# darwin-radio.net
KiCad netlist of a schematic drawn in EAGLE
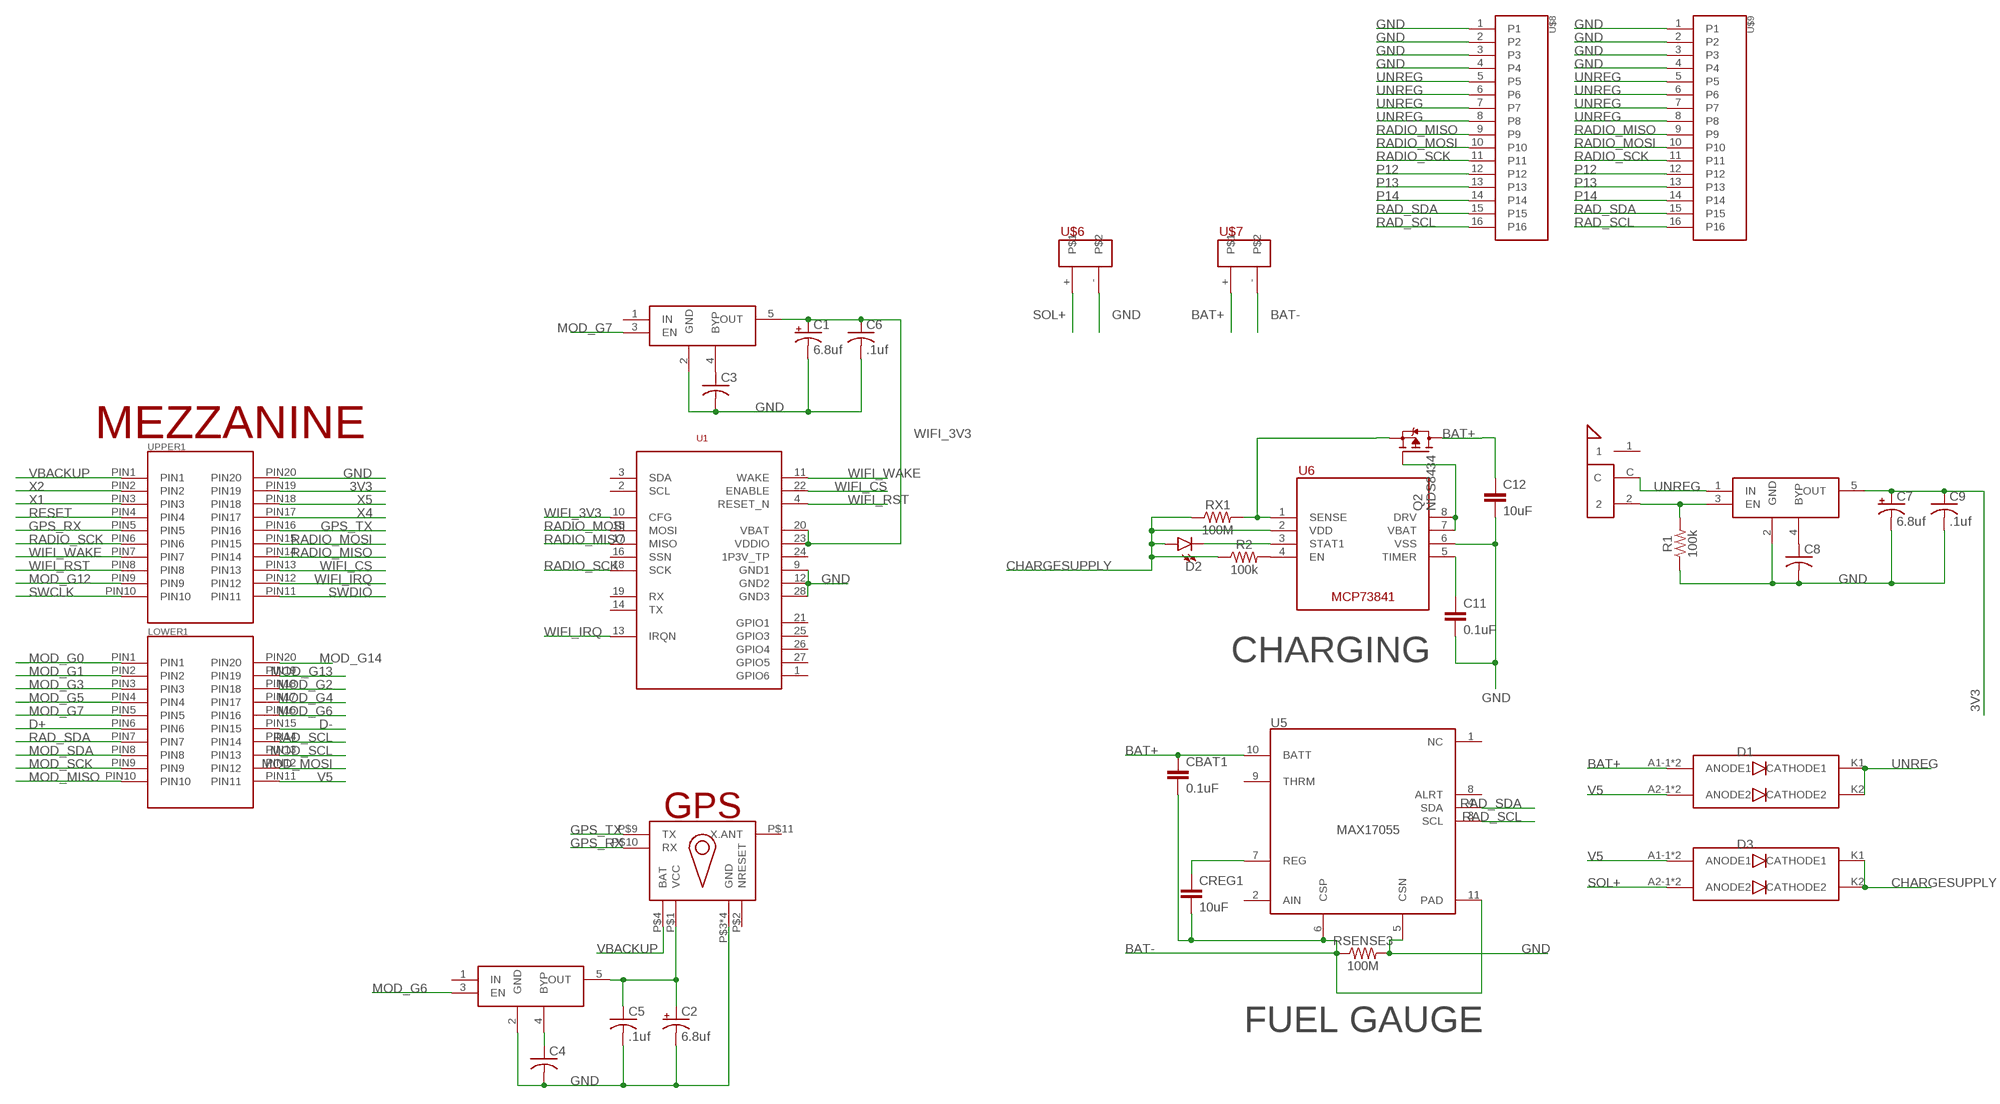
[diagram p0: schematic, sheet 1]

(export (version "E")
  (design (tool "Eeschema 10.0.6"))
  (components
    (comp (ref "C1")
      (value "6.8uf")
      (footprint "eagle-import:A_3216-18R")
      (libsource (lib "eagle-import") (part "CPOL-USA/3216-18R"))
    )
    (comp (ref "C2")
      (value "6.8uf")
      (footprint "eagle-import:A_3216-18R")
      (libsource (lib "eagle-import") (part "CPOL-USA/3216-18R"))
    )
    (comp (ref "C3")
      (value "C-USC0603K")
      (footprint "eagle-import:C0603K")
      (libsource (lib "eagle-import") (part "C-USC0603K"))
    )
    (comp (ref "C4")
      (value "C-USC0603K")
      (footprint "eagle-import:C0603K")
      (libsource (lib "eagle-import") (part "C-USC0603K"))
    )
    (comp (ref "C5")
      (value ".1uf")
      (footprint "eagle-import:C0603K")
      (libsource (lib "eagle-import") (part "C-USC0603K"))
    )
    (comp (ref "C6")
      (value ".1uf")
      (footprint "eagle-import:C0603K")
      (libsource (lib "eagle-import") (part "C-USC0603K"))
    )
    (comp (ref "C7")
      (value "6.8uf")
      (footprint "eagle-import:A_3216-18R")
      (libsource (lib "eagle-import") (part "CPOL-USA/3216-18R"))
    )
    (comp (ref "C8")
      (value "C-USC0603K")
      (footprint "eagle-import:C0603K")
      (libsource (lib "eagle-import") (part "C-USC0603K"))
    )
    (comp (ref "C9")
      (value ".1uf")
      (footprint "eagle-import:C0603K")
      (libsource (lib "eagle-import") (part "C-USC0603K"))
    )
    (comp (ref "C11")
      (value "0.1uF")
      (footprint "eagle-import:0603")
      (libsource (lib "eagle-import") (part "0.1UF-0603-25V-(+80/-20%)"))
    )
    (comp (ref "C12")
      (value "10uF")
      (footprint "eagle-import:0603")
      (libsource (lib "eagle-import") (part "10UF-0603-6.3V-20%"))
    )
    (comp (ref "CBAT1")
      (value "0.1uF")
      (footprint "eagle-import:0603")
      (libsource (lib "eagle-import") (part "0.1UF-0603-25V-(+80/-20%)"))
    )
    (comp (ref "CREG1")
      (value "10uF")
      (footprint "eagle-import:0603")
      (libsource (lib "eagle-import") (part "10UF-0603-6.3V-20%"))
    )
    (comp (ref "D1")
      (value "V10KL45DUHM3/H")
      (footprint "eagle-import:V10KL45DUHM3_H")
      (libsource (lib "eagle-import") (part "V10KL45DUHM3/H"))
    )
    (comp (ref "D2")
      (value "LED0603")
      (footprint "eagle-import:LED-0603")
      (libsource (lib "eagle-import") (part "LED0603"))
    )
    (comp (ref "D3")
      (value "V10KL45DUHM3/H")
      (footprint "eagle-import:V10KL45DUHM3_H")
      (libsource (lib "eagle-import") (part "V10KL45DUHM3/H"))
    )
    (comp (ref "LOWER1")
      (value "MOLEX-15-91-2200")
      (footprint "eagle-import:20PH")
      (libsource (lib "eagle-import") (part "MOLEX-15-91-2200"))
    )
    (comp (ref "Q2")
      (value "NDS8434")
      (footprint "eagle-import:SO08-IRF")
      (libsource (lib "eagle-import") (part "NDS8434"))
    )
    (comp (ref "R1")
      (value "100k")
      (footprint "eagle-import:0603")
      (libsource (lib "eagle-import") (part "100KOHM-0603-1/10W-1%"))
    )
    (comp (ref "R2")
      (value "100k")
      (footprint "eagle-import:0603")
      (libsource (lib "eagle-import") (part "100KOHM-0603-1/10W-1%"))
    )
    (comp (ref "RSENSE3")
      (value "100M")
      (footprint "eagle-import:0603")
      (libsource (lib "eagle-import") (part "1MOHM-0603-1/4W-5%"))
    )
    (comp (ref "RX1")
      (value "100M")
      (footprint "eagle-import:0603")
      (libsource (lib "eagle-import") (part "1MOHM-0603-1/4W-5%"))
    )
    (comp (ref "U$1")
      (value "FGPMMOPA6H")
      (footprint "eagle-import:GPS_MODULE")
      (libsource (lib "eagle-import") (part "FGPMMOPA6H"))
    )
    (comp (ref "U$2")
      (value "MIC5219-3.3YM5-TR")
      (footprint "eagle-import:SOT95P280X145-5")
      (libsource (lib "eagle-import") (part "MIC5219-3.3YM5-TR"))
    )
    (comp (ref "U$3")
      (value "MIC5219-3.3YM5-TR")
      (footprint "eagle-import:SOT95P280X145-5")
      (libsource (lib "eagle-import") (part "MIC5219-3.3YM5-TR"))
    )
    (comp (ref "U$4")
      (value "MIC5219-3.3YM5-TR")
      (footprint "eagle-import:SOT95P280X145-5")
      (libsource (lib "eagle-import") (part "MIC5219-3.3YM5-TR"))
    )
    (comp (ref "U$5")
      (value "SSAJ110100")
      (footprint "eagle-import:SSAJ110100")
      (libsource (lib "eagle-import") (part "SSAJ110100"))
    )
    (comp (ref "U$6")
      (value "B2B-PH-SM4-TB")
      (footprint "eagle-import:B2B-PH-SM4-TB")
      (libsource (lib "eagle-import") (part "B2B-PH-SM4-TB"))
    )
    (comp (ref "U$7")
      (value "B2B-PH-SM4-TB")
      (footprint "eagle-import:B2B-PH-SM4-TB")
      (libsource (lib "eagle-import") (part "B2B-PH-SM4-TB"))
    )
    (comp (ref "U$8")
      (value "505110-1692")
      (footprint "eagle-import:505110-1692")
      (libsource (lib "eagle-import") (part "505110-1692"))
    )
    (comp (ref "U$9")
      (value "505110-1692")
      (footprint "eagle-import:505110-1692")
      (libsource (lib "eagle-import") (part "505110-1692"))
    )
    (comp (ref "U1")
      (value "ATWINC")
      (footprint "eagle-import:ATWINC")
      (libsource (lib "eagle-import") (part "ATWINC"))
    )
    (comp (ref "U5")
      (value "MAX17055")
      (footprint "eagle-import:SON50P300X300X75-11T150X230")
      (libsource (lib "eagle-import") (part "MAX17055"))
    )
    (comp (ref "U6")
      (value "MCP7384X")
      (footprint "eagle-import:SOP65P490X110-8")
      (libsource (lib "eagle-import") (part "MCP7384X"))
    )
    (comp (ref "UPPER1")
      (value "MOLEX-15-91-2200")
      (footprint "eagle-import:20PH")
      (libsource (lib "eagle-import") (part "MOLEX-15-91-2200"))
    )
  )
  (nets
    (net (code "1") (name "/3V3") (class "Default")
      (node (ref "C7") (pin "+") (pinfunction "+_+") (pintype "passive"))
      (node (ref "C9") (pin "1") (pinfunction "1_1") (pintype "passive"))
      (node (ref "U$4") (pin "5") (pinfunction "OUT_5") (pintype "bidirectional"))
      (node (ref "UPPER1") (pin "PIN19") (pinfunction "PIN19_PIN19") (pintype "bidirectional"))
    )
    (net (code "2") (name "/BAT+") (class "Default")
      (node (ref "C12") (pin "1") (pinfunction "1_1") (pintype "passive"))
      (node (ref "CBAT1") (pin "1") (pinfunction "1_1") (pintype "passive"))
      (node (ref "D1") (pin "A1-1") (pinfunction "ANODE1_A1-1") (pintype "bidirectional"))
      (node (ref "D1") (pin "A1-2") (pinfunction "ANODE1_A1-2") (pintype "bidirectional"))
      (node (ref "Q2") (pin "5") (pinfunction "D_5") (pintype "passive"))
      (node (ref "Q2") (pin "6") (pinfunction "D_6") (pintype "passive"))
      (node (ref "Q2") (pin "7") (pinfunction "D_7") (pintype "passive"))
      (node (ref "Q2") (pin "8") (pinfunction "D_8") (pintype "passive"))
      (node (ref "U$7") (pin "+") (pinfunction "P$1_+") (pintype "bidirectional"))
      (node (ref "U5") (pin "10") (pinfunction "BATT_10") (pintype "bidirectional"))
    )
    (net (code "3") (name "/BAT-") (class "Default")
      (node (ref "CBAT1") (pin "2") (pinfunction "2_2") (pintype "passive"))
      (node (ref "CREG1") (pin "2") (pinfunction "2_2") (pintype "passive"))
      (node (ref "RSENSE3") (pin "1") (pinfunction "1_1") (pintype "passive"))
      (node (ref "U$7") (pin "-") (pinfunction "P$2_-") (pintype "bidirectional"))
      (node (ref "U5") (pin "11") (pinfunction "PAD_11") (pintype "bidirectional"))
      (node (ref "U5") (pin "6") (pinfunction "CSP_6") (pintype "bidirectional"))
    )
    (net (code "4") (name "/CHARGESUPPLY") (class "Default")
      (node (ref "D2") (pin "A") (pinfunction "A_A") (pintype "passive"))
      (node (ref "D3") (pin "K1") (pinfunction "CATHODE1_K1") (pintype "bidirectional"))
      (node (ref "D3") (pin "K2") (pinfunction "CATHODE2_K2") (pintype "bidirectional"))
      (node (ref "R2") (pin "1") (pinfunction "1_1") (pintype "passive"))
      (node (ref "RX1") (pin "1") (pinfunction "1_1") (pintype "passive"))
      (node (ref "U6") (pin "2") (pinfunction "VDD_2") (pintype "bidirectional"))
    )
    (net (code "5") (name "/D+") (class "Default")
      (node (ref "LOWER1") (pin "PIN6") (pinfunction "PIN6_PIN6") (pintype "bidirectional"))
    )
    (net (code "6") (name "/D-") (class "Default")
      (node (ref "LOWER1") (pin "PIN15") (pinfunction "PIN15_PIN15") (pintype "bidirectional"))
    )
    (net (code "7") (name "/GND") (class "Default")
      (node (ref "C1") (pin "-") (pinfunction "-_-") (pintype "passive"))
      (node (ref "C11") (pin "2") (pinfunction "2_2") (pintype "passive"))
      (node (ref "C12") (pin "2") (pinfunction "2_2") (pintype "passive"))
      (node (ref "C2") (pin "-") (pinfunction "-_-") (pintype "passive"))
      (node (ref "C3") (pin "2") (pinfunction "2_2") (pintype "passive"))
      (node (ref "C4") (pin "2") (pinfunction "2_2") (pintype "passive"))
      (node (ref "C5") (pin "2") (pinfunction "2_2") (pintype "passive"))
      (node (ref "C6") (pin "2") (pinfunction "2_2") (pintype "passive"))
      (node (ref "C7") (pin "-") (pinfunction "-_-") (pintype "passive"))
      (node (ref "C8") (pin "2") (pinfunction "2_2") (pintype "passive"))
      (node (ref "C9") (pin "2") (pinfunction "2_2") (pintype "passive"))
      (node (ref "R1") (pin "1") (pinfunction "1_1") (pintype "passive"))
      (node (ref "RSENSE3") (pin "2") (pinfunction "2_2") (pintype "passive"))
      (node (ref "U$1") (pin "P$12") (pinfunction "GND_P$12") (pintype "bidirectional"))
      (node (ref "U$1") (pin "P$19") (pinfunction "GND_P$19") (pintype "bidirectional"))
      (node (ref "U$1") (pin "P$3") (pinfunction "GND_P$3") (pintype "bidirectional"))
      (node (ref "U$1") (pin "P$8") (pinfunction "GND_P$8") (pintype "bidirectional"))
      (node (ref "U$2") (pin "2") (pinfunction "GND_2") (pintype "bidirectional"))
      (node (ref "U$3") (pin "2") (pinfunction "GND_2") (pintype "bidirectional"))
      (node (ref "U$4") (pin "2") (pinfunction "GND_2") (pintype "bidirectional"))
      (node (ref "U$6") (pin "-") (pinfunction "P$2_-") (pintype "bidirectional"))
      (node (ref "U$8") (pin "1") (pinfunction "P1_1") (pintype "bidirectional"))
      (node (ref "U$8") (pin "2") (pinfunction "P2_2") (pintype "bidirectional"))
      (node (ref "U$8") (pin "3") (pinfunction "P3_3") (pintype "bidirectional"))
      (node (ref "U$8") (pin "4") (pinfunction "P4_4") (pintype "bidirectional"))
      (node (ref "U$9") (pin "1") (pinfunction "P1_1") (pintype "bidirectional"))
      (node (ref "U$9") (pin "2") (pinfunction "P2_2") (pintype "bidirectional"))
      (node (ref "U$9") (pin "3") (pinfunction "P3_3") (pintype "bidirectional"))
      (node (ref "U$9") (pin "4") (pinfunction "P4_4") (pintype "bidirectional"))
      (node (ref "U1") (pin "12") (pinfunction "GND2_12") (pintype "bidirectional"))
      (node (ref "U1") (pin "28") (pinfunction "GND3_28") (pintype "bidirectional"))
      (node (ref "U1") (pin "9") (pinfunction "GND1_9") (pintype "bidirectional"))
      (node (ref "U5") (pin "5") (pinfunction "CSN_5") (pintype "bidirectional"))
      (node (ref "U6") (pin "6") (pinfunction "VSS_6") (pintype "bidirectional"))
      (node (ref "UPPER1") (pin "PIN20") (pinfunction "PIN20_PIN20") (pintype "bidirectional"))
    )
    (net (code "8") (name "/GPS_RX") (class "Default")
      (node (ref "U$1") (pin "P$10") (pinfunction "RX_P$10") (pintype "bidirectional"))
      (node (ref "UPPER1") (pin "PIN5") (pinfunction "PIN5_PIN5") (pintype "bidirectional"))
    )
    (net (code "9") (name "/GPS_TX") (class "Default")
      (node (ref "U$1") (pin "P$9") (pinfunction "TX_P$9") (pintype "bidirectional"))
      (node (ref "UPPER1") (pin "PIN16") (pinfunction "PIN16_PIN16") (pintype "bidirectional"))
    )
    (net (code "10") (name "/MOD_G0") (class "Default")
      (node (ref "LOWER1") (pin "PIN1") (pinfunction "PIN1_PIN1") (pintype "bidirectional"))
    )
    (net (code "11") (name "/MOD_G1") (class "Default")
      (node (ref "LOWER1") (pin "PIN2") (pinfunction "PIN2_PIN2") (pintype "bidirectional"))
    )
    (net (code "12") (name "/MOD_G2") (class "Default")
      (node (ref "LOWER1") (pin "PIN18") (pinfunction "PIN18_PIN18") (pintype "bidirectional"))
    )
    (net (code "13") (name "/MOD_G3") (class "Default")
      (node (ref "LOWER1") (pin "PIN3") (pinfunction "PIN3_PIN3") (pintype "bidirectional"))
    )
    (net (code "14") (name "/MOD_G4") (class "Default")
      (node (ref "LOWER1") (pin "PIN17") (pinfunction "PIN17_PIN17") (pintype "bidirectional"))
    )
    (net (code "15") (name "/MOD_G5") (class "Default")
      (node (ref "LOWER1") (pin "PIN4") (pinfunction "PIN4_PIN4") (pintype "bidirectional"))
    )
    (net (code "16") (name "/MOD_G6") (class "Default")
      (node (ref "LOWER1") (pin "PIN16") (pinfunction "PIN16_PIN16") (pintype "bidirectional"))
      (node (ref "U$2") (pin "3") (pinfunction "EN_3") (pintype "bidirectional"))
    )
    (net (code "17") (name "/MOD_G7") (class "Default")
      (node (ref "LOWER1") (pin "PIN5") (pinfunction "PIN5_PIN5") (pintype "bidirectional"))
      (node (ref "U$3") (pin "3") (pinfunction "EN_3") (pintype "bidirectional"))
    )
    (net (code "18") (name "/MOD_G12") (class "Default")
      (node (ref "UPPER1") (pin "PIN9") (pinfunction "PIN9_PIN9") (pintype "bidirectional"))
    )
    (net (code "19") (name "/MOD_G13") (class "Default")
      (node (ref "LOWER1") (pin "PIN19") (pinfunction "PIN19_PIN19") (pintype "bidirectional"))
    )
    (net (code "20") (name "/MOD_G14") (class "Default")
      (node (ref "LOWER1") (pin "PIN20") (pinfunction "PIN20_PIN20") (pintype "bidirectional"))
    )
    (net (code "21") (name "/MOD_MISO") (class "Default")
      (node (ref "LOWER1") (pin "PIN10") (pinfunction "PIN10_PIN10") (pintype "bidirectional"))
    )
    (net (code "22") (name "/MOD_MOSI") (class "Default")
      (node (ref "LOWER1") (pin "PIN12") (pinfunction "PIN12_PIN12") (pintype "bidirectional"))
    )
    (net (code "23") (name "/MOD_SCK") (class "Default")
      (node (ref "LOWER1") (pin "PIN9") (pinfunction "PIN9_PIN9") (pintype "bidirectional"))
    )
    (net (code "24") (name "/MOD_SCL") (class "Default")
      (node (ref "LOWER1") (pin "PIN13") (pinfunction "PIN13_PIN13") (pintype "bidirectional"))
    )
    (net (code "25") (name "/MOD_SDA") (class "Default")
      (node (ref "LOWER1") (pin "PIN8") (pinfunction "PIN8_PIN8") (pintype "bidirectional"))
    )
    (net (code "26") (name "/P12") (class "Default")
      (node (ref "U$8") (pin "12") (pinfunction "P12_12") (pintype "bidirectional"))
      (node (ref "U$9") (pin "12") (pinfunction "P12_12") (pintype "bidirectional"))
    )
    (net (code "27") (name "/P13") (class "Default")
      (node (ref "U$8") (pin "13") (pinfunction "P13_13") (pintype "bidirectional"))
      (node (ref "U$9") (pin "13") (pinfunction "P13_13") (pintype "bidirectional"))
    )
    (net (code "28") (name "/P14") (class "Default")
      (node (ref "U$8") (pin "14") (pinfunction "P14_14") (pintype "bidirectional"))
      (node (ref "U$9") (pin "14") (pinfunction "P14_14") (pintype "bidirectional"))
    )
    (net (code "29") (name "/RADIO_MISO") (class "Default")
      (node (ref "U$8") (pin "9") (pinfunction "P9_9") (pintype "bidirectional"))
      (node (ref "U$9") (pin "9") (pinfunction "P9_9") (pintype "bidirectional"))
      (node (ref "U1") (pin "17") (pinfunction "MISO_17") (pintype "bidirectional"))
      (node (ref "UPPER1") (pin "PIN14") (pinfunction "PIN14_PIN14") (pintype "bidirectional"))
    )
    (net (code "30") (name "/RADIO_MOSI") (class "Default")
      (node (ref "U$8") (pin "10") (pinfunction "P10_10") (pintype "bidirectional"))
      (node (ref "U$9") (pin "10") (pinfunction "P10_10") (pintype "bidirectional"))
      (node (ref "U1") (pin "15") (pinfunction "MOSI_15") (pintype "bidirectional"))
      (node (ref "UPPER1") (pin "PIN15") (pinfunction "PIN15_PIN15") (pintype "bidirectional"))
    )
    (net (code "31") (name "/RADIO_SCK") (class "Default")
      (node (ref "U$8") (pin "11") (pinfunction "P11_11") (pintype "bidirectional"))
      (node (ref "U$9") (pin "11") (pinfunction "P11_11") (pintype "bidirectional"))
      (node (ref "U1") (pin "18") (pinfunction "SCK_18") (pintype "bidirectional"))
      (node (ref "UPPER1") (pin "PIN6") (pinfunction "PIN6_PIN6") (pintype "bidirectional"))
    )
    (net (code "32") (name "/RAD_SCL") (class "Default")
      (node (ref "LOWER1") (pin "PIN14") (pinfunction "PIN14_PIN14") (pintype "bidirectional"))
      (node (ref "U$8") (pin "16") (pinfunction "P16_16") (pintype "bidirectional"))
      (node (ref "U$9") (pin "16") (pinfunction "P16_16") (pintype "bidirectional"))
      (node (ref "U5") (pin "3") (pinfunction "SCL_3") (pintype "bidirectional"))
    )
    (net (code "33") (name "/RAD_SDA") (class "Default")
      (node (ref "LOWER1") (pin "PIN7") (pinfunction "PIN7_PIN7") (pintype "bidirectional"))
      (node (ref "U$8") (pin "15") (pinfunction "P15_15") (pintype "bidirectional"))
      (node (ref "U$9") (pin "15") (pinfunction "P15_15") (pintype "bidirectional"))
      (node (ref "U5") (pin "4") (pinfunction "SDA_4") (pintype "bidirectional"))
    )
    (net (code "34") (name "/RESET") (class "Default")
      (node (ref "UPPER1") (pin "PIN4") (pinfunction "PIN4_PIN4") (pintype "bidirectional"))
    )
    (net (code "35") (name "/SOL+") (class "Default")
      (node (ref "D3") (pin "A2-1") (pinfunction "ANODE2_A2-1") (pintype "bidirectional"))
      (node (ref "D3") (pin "A2-2") (pinfunction "ANODE2_A2-2") (pintype "bidirectional"))
      (node (ref "U$6") (pin "+") (pinfunction "P$1_+") (pintype "bidirectional"))
    )
    (net (code "36") (name "/SWCLK") (class "Default")
      (node (ref "UPPER1") (pin "PIN10") (pinfunction "PIN10_PIN10") (pintype "bidirectional"))
    )
    (net (code "37") (name "/SWDIO") (class "Default")
      (node (ref "UPPER1") (pin "PIN11") (pinfunction "PIN11_PIN11") (pintype "bidirectional"))
    )
    (net (code "38") (name "/UNREG") (class "Default")
      (node (ref "D1") (pin "K1") (pinfunction "CATHODE1_K1") (pintype "bidirectional"))
      (node (ref "D1") (pin "K2") (pinfunction "CATHODE2_K2") (pintype "bidirectional"))
      (node (ref "U$4") (pin "1") (pinfunction "IN_1") (pintype "bidirectional"))
      (node (ref "U$5") (pin "C") (pinfunction "C_C") (pintype "bidirectional"))
      (node (ref "U$8") (pin "5") (pinfunction "P5_5") (pintype "bidirectional"))
      (node (ref "U$8") (pin "6") (pinfunction "P6_6") (pintype "bidirectional"))
      (node (ref "U$8") (pin "7") (pinfunction "P7_7") (pintype "bidirectional"))
      (node (ref "U$8") (pin "8") (pinfunction "P8_8") (pintype "bidirectional"))
      (node (ref "U$9") (pin "5") (pinfunction "P5_5") (pintype "bidirectional"))
      (node (ref "U$9") (pin "6") (pinfunction "P6_6") (pintype "bidirectional"))
      (node (ref "U$9") (pin "7") (pinfunction "P7_7") (pintype "bidirectional"))
      (node (ref "U$9") (pin "8") (pinfunction "P8_8") (pintype "bidirectional"))
    )
    (net (code "39") (name "/V5") (class "Default")
      (node (ref "D1") (pin "A2-1") (pinfunction "ANODE2_A2-1") (pintype "bidirectional"))
      (node (ref "D1") (pin "A2-2") (pinfunction "ANODE2_A2-2") (pintype "bidirectional"))
      (node (ref "D3") (pin "A1-1") (pinfunction "ANODE1_A1-1") (pintype "bidirectional"))
      (node (ref "D3") (pin "A1-2") (pinfunction "ANODE1_A1-2") (pintype "bidirectional"))
      (node (ref "LOWER1") (pin "PIN11") (pinfunction "PIN11_PIN11") (pintype "bidirectional"))
    )
    (net (code "40") (name "/VBACKUP") (class "Default")
      (node (ref "U$1") (pin "P$4") (pinfunction "BAT_P$4") (pintype "bidirectional"))
      (node (ref "UPPER1") (pin "PIN1") (pinfunction "PIN1_PIN1") (pintype "bidirectional"))
    )
    (net (code "41") (name "/WIFI_3V3") (class "Default")
      (node (ref "C1") (pin "+") (pinfunction "+_+") (pintype "passive"))
      (node (ref "C6") (pin "1") (pinfunction "1_1") (pintype "passive"))
      (node (ref "U$3") (pin "5") (pinfunction "OUT_5") (pintype "bidirectional"))
      (node (ref "U1") (pin "10") (pinfunction "CFG_10") (pintype "bidirectional"))
      (node (ref "U1") (pin "20") (pinfunction "VBAT_20") (pintype "bidirectional"))
      (node (ref "U1") (pin "23") (pinfunction "VDDIO_23") (pintype "bidirectional"))
    )
    (net (code "42") (name "/WIFI_CS") (class "Default")
      (node (ref "U1") (pin "22") (pinfunction "ENABLE_22") (pintype "bidirectional"))
      (node (ref "UPPER1") (pin "PIN13") (pinfunction "PIN13_PIN13") (pintype "bidirectional"))
    )
    (net (code "43") (name "/WIFI_IRQ") (class "Default")
      (node (ref "U1") (pin "13") (pinfunction "IRQN_13") (pintype "bidirectional"))
      (node (ref "UPPER1") (pin "PIN12") (pinfunction "PIN12_PIN12") (pintype "bidirectional"))
    )
    (net (code "44") (name "/WIFI_RST") (class "Default")
      (node (ref "U1") (pin "4") (pinfunction "RESET_N_4") (pintype "bidirectional"))
      (node (ref "UPPER1") (pin "PIN8") (pinfunction "PIN8_PIN8") (pintype "bidirectional"))
    )
    (net (code "45") (name "/WIFI_WAKE") (class "Default")
      (node (ref "U1") (pin "11") (pinfunction "WAKE_11") (pintype "bidirectional"))
      (node (ref "UPPER1") (pin "PIN7") (pinfunction "PIN7_PIN7") (pintype "bidirectional"))
    )
    (net (code "46") (name "/X1") (class "Default")
      (node (ref "UPPER1") (pin "PIN3") (pinfunction "PIN3_PIN3") (pintype "bidirectional"))
    )
    (net (code "47") (name "/X2") (class "Default")
      (node (ref "UPPER1") (pin "PIN2") (pinfunction "PIN2_PIN2") (pintype "bidirectional"))
    )
    (net (code "48") (name "/X4") (class "Default")
      (node (ref "UPPER1") (pin "PIN17") (pinfunction "PIN17_PIN17") (pintype "bidirectional"))
    )
    (net (code "49") (name "/X5") (class "Default")
      (node (ref "UPPER1") (pin "PIN18") (pinfunction "PIN18_PIN18") (pintype "bidirectional"))
    )
    (net (code "50") (name "Net-(Q2-G)") (class "Default")
      (node (ref "Q2") (pin "4") (pinfunction "G_4") (pintype "passive"))
      (node (ref "U6") (pin "7") (pinfunction "VBAT_7") (pintype "bidirectional"))
      (node (ref "U6") (pin "8") (pinfunction "DRV_8") (pintype "bidirectional"))
    )
    (net (code "51") (name "Net-(U$1-VCC)") (class "Default")
      (node (ref "C2") (pin "+") (pinfunction "+_+") (pintype "passive"))
      (node (ref "C5") (pin "1") (pinfunction "1_1") (pintype "passive"))
      (node (ref "U$1") (pin "P$1") (pinfunction "VCC_P$1") (pintype "bidirectional"))
      (node (ref "U$2") (pin "5") (pinfunction "OUT_5") (pintype "bidirectional"))
    )
    (net (code "52") (name "Net-(U$2-BYP)") (class "Default")
      (node (ref "C4") (pin "1") (pinfunction "1_1") (pintype "passive"))
      (node (ref "U$2") (pin "4") (pinfunction "BYP_4") (pintype "bidirectional"))
    )
    (net (code "53") (name "Net-(U$3-BYP)") (class "Default")
      (node (ref "C3") (pin "1") (pinfunction "1_1") (pintype "passive"))
      (node (ref "U$3") (pin "4") (pinfunction "BYP_4") (pintype "bidirectional"))
    )
    (net (code "54") (name "Net-(U$4-BYP)") (class "Default")
      (node (ref "C8") (pin "1") (pinfunction "1_1") (pintype "passive"))
      (node (ref "U$4") (pin "4") (pinfunction "BYP_4") (pintype "bidirectional"))
    )
    (net (code "55") (name "Net-(U$4-EN)") (class "Default")
      (node (ref "R1") (pin "2") (pinfunction "2_2") (pintype "passive"))
      (node (ref "U$4") (pin "3") (pinfunction "EN_3") (pintype "bidirectional"))
      (node (ref "U$5") (pin "2") (pinfunction "2_2") (pintype "bidirectional"))
    )
    (net (code "56") (name "Net-(U5-REG)") (class "Default")
      (node (ref "CREG1") (pin "1") (pinfunction "1_1") (pintype "passive"))
      (node (ref "U5") (pin "7") (pinfunction "REG_7") (pintype "bidirectional"))
    )
    (net (code "57") (name "Net-(U6-EN)") (class "Default")
      (node (ref "R2") (pin "2") (pinfunction "2_2") (pintype "passive"))
      (node (ref "U6") (pin "4") (pinfunction "EN_4") (pintype "bidirectional"))
    )
    (net (code "58") (name "Net-(U6-SENSE)") (class "Default")
      (node (ref "Q2") (pin "1") (pinfunction "S_1") (pintype "passive"))
      (node (ref "Q2") (pin "2") (pinfunction "S_2") (pintype "passive"))
      (node (ref "Q2") (pin "3") (pinfunction "S_3") (pintype "passive"))
      (node (ref "RX1") (pin "2") (pinfunction "2_2") (pintype "passive"))
      (node (ref "U6") (pin "1") (pinfunction "SENSE_1") (pintype "bidirectional"))
    )
    (net (code "59") (name "Net-(U6-STAT1)") (class "Default")
      (node (ref "D2") (pin "C") (pinfunction "C_C") (pintype "passive"))
      (node (ref "U6") (pin "3") (pinfunction "STAT1_3") (pintype "bidirectional"))
    )
    (net (code "60") (name "Net-(U6-TIMER)") (class "Default")
      (node (ref "C11") (pin "1") (pinfunction "1_1") (pintype "passive"))
      (node (ref "U6") (pin "5") (pinfunction "TIMER_5") (pintype "bidirectional"))
    )
    (net (code "61") (name "unconnected-(U$1-NRESET-PadP$2)") (class "Default")
      (node (ref "U$1") (pin "P$2") (pinfunction "NRESET_P$2") (pintype "bidirectional"))
    )
    (net (code "62") (name "unconnected-(U$1-X.ANT-PadP$11)") (class "Default")
      (node (ref "U$1") (pin "P$11") (pinfunction "X.ANT_P$11") (pintype "bidirectional"))
    )
    (net (code "63") (name "unconnected-(U$2-IN-Pad1)") (class "Default")
      (node (ref "U$2") (pin "1") (pinfunction "IN_1") (pintype "bidirectional"))
    )
    (net (code "64") (name "unconnected-(U$3-IN-Pad1)") (class "Default")
      (node (ref "U$3") (pin "1") (pinfunction "IN_1") (pintype "bidirectional"))
    )
    (net (code "65") (name "unconnected-(U$5-Pad1)") (class "Default")
      (node (ref "U$5") (pin "1") (pinfunction "1_1") (pintype "bidirectional"))
    )
    (net (code "66") (name "unconnected-(U1-1P3V_TP-Pad24)") (class "Default")
      (node (ref "U1") (pin "24") (pinfunction "1P3V_TP_24") (pintype "bidirectional"))
    )
    (net (code "67") (name "unconnected-(U1-GPIO1-Pad21)") (class "Default")
      (node (ref "U1") (pin "21") (pinfunction "GPIO1_21") (pintype "bidirectional"))
    )
    (net (code "68") (name "unconnected-(U1-GPIO3-Pad25)") (class "Default")
      (node (ref "U1") (pin "25") (pinfunction "GPIO3_25") (pintype "bidirectional"))
    )
    (net (code "69") (name "unconnected-(U1-GPIO4-Pad26)") (class "Default")
      (node (ref "U1") (pin "26") (pinfunction "GPIO4_26") (pintype "bidirectional"))
    )
    (net (code "70") (name "unconnected-(U1-GPIO5-Pad27)") (class "Default")
      (node (ref "U1") (pin "27") (pinfunction "GPIO5_27") (pintype "bidirectional"))
    )
    (net (code "71") (name "unconnected-(U1-GPIO6-Pad1)") (class "Default")
      (node (ref "U1") (pin "1") (pinfunction "GPIO6_1") (pintype "bidirectional"))
    )
    (net (code "72") (name "unconnected-(U1-RX-Pad19)") (class "Default")
      (node (ref "U1") (pin "19") (pinfunction "RX_19") (pintype "bidirectional"))
    )
    (net (code "73") (name "unconnected-(U1-SCL-Pad2)") (class "Default")
      (node (ref "U1") (pin "2") (pinfunction "SCL_2") (pintype "bidirectional"))
    )
    (net (code "74") (name "unconnected-(U1-SDA-Pad3)") (class "Default")
      (node (ref "U1") (pin "3") (pinfunction "SDA_3") (pintype "bidirectional"))
    )
    (net (code "75") (name "unconnected-(U1-SSN-Pad16)") (class "Default")
      (node (ref "U1") (pin "16") (pinfunction "SSN_16") (pintype "bidirectional"))
    )
    (net (code "76") (name "unconnected-(U1-TX-Pad14)") (class "Default")
      (node (ref "U1") (pin "14") (pinfunction "TX_14") (pintype "bidirectional"))
    )
    (net (code "77") (name "unconnected-(U5-AIN-Pad2)") (class "Default")
      (node (ref "U5") (pin "2") (pinfunction "AIN_2") (pintype "bidirectional"))
    )
    (net (code "78") (name "unconnected-(U5-ALRT-Pad8)") (class "Default")
      (node (ref "U5") (pin "8") (pinfunction "ALRT_8") (pintype "bidirectional"))
    )
    (net (code "79") (name "unconnected-(U5-NC-Pad1)") (class "Default")
      (node (ref "U5") (pin "1") (pinfunction "NC_1") (pintype "bidirectional"))
    )
    (net (code "80") (name "unconnected-(U5-THRM-Pad9)") (class "Default")
      (node (ref "U5") (pin "9") (pinfunction "THRM_9") (pintype "bidirectional"))
    )
  )
)
